# driver_board_v00.net
KiCad netlist of a schematic drawn in EAGLE
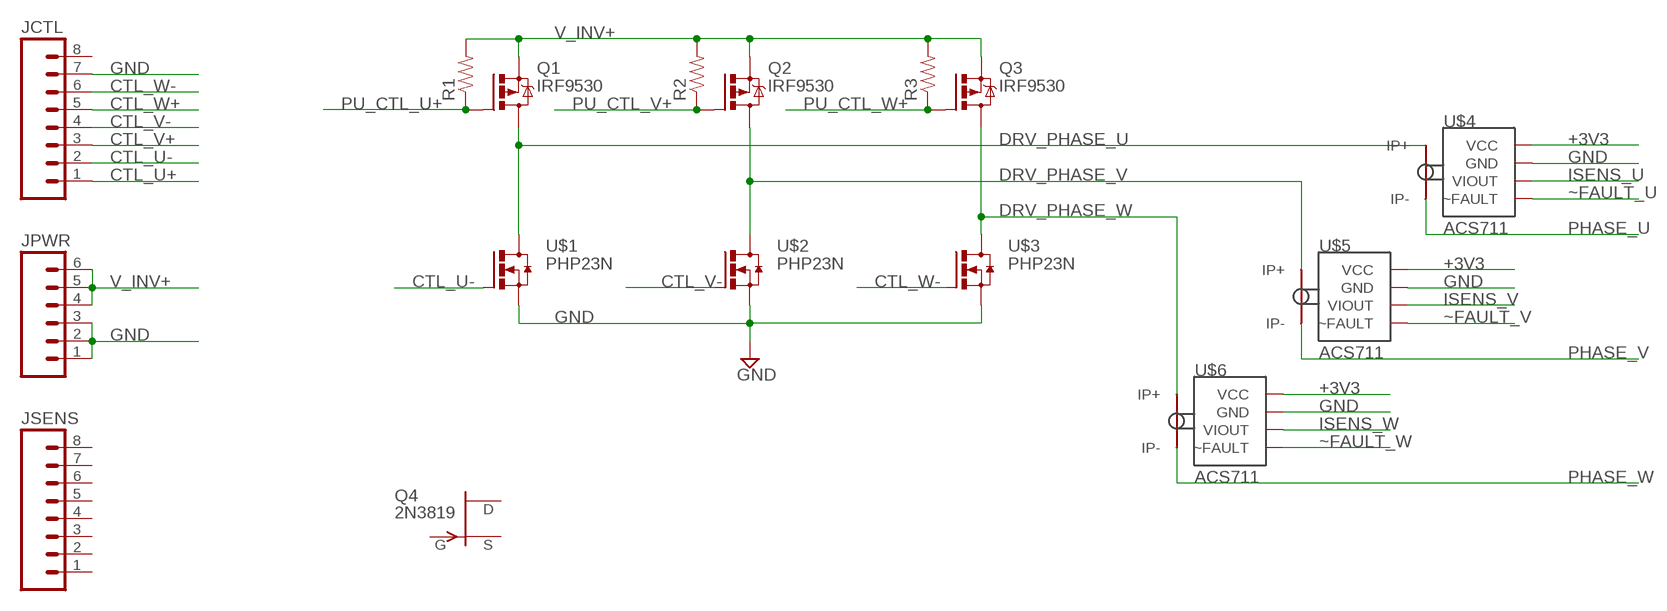
[diagram p0: schematic, sheet 1]

(export (version "E")
  (design (tool "Eeschema 10.0.6"))
  (components
    (comp (ref "JCTL")
      (value "M08LOCK")
      (footprint "eagle-import:1X08_LOCK")
      (libsource (lib "eagle-import") (part "M08LOCK"))
    )
    (comp (ref "JPWR")
      (value "M06LOCK")
      (footprint "eagle-import:1X06_LOCK")
      (libsource (lib "eagle-import") (part "M06LOCK"))
    )
    (comp (ref "JSENS")
      (value "M08LOCK")
      (footprint "eagle-import:1X08_LOCK")
      (libsource (lib "eagle-import") (part "M08LOCK"))
    )
    (comp (ref "Q1")
      (value "IRF9530")
      (footprint "eagle-import:TO220BV")
      (libsource (lib "eagle-import") (part "IRF9530"))
    )
    (comp (ref "Q2")
      (value "IRF9530")
      (footprint "eagle-import:TO220BV")
      (libsource (lib "eagle-import") (part "IRF9530"))
    )
    (comp (ref "Q3")
      (value "IRF9530")
      (footprint "eagle-import:TO220BV")
      (libsource (lib "eagle-import") (part "IRF9530"))
    )
    (comp (ref "Q4")
      (value "2N3819")
      (footprint "eagle-import:TO92")
      (libsource (lib "eagle-import") (part "2N3819"))
    )
    (comp (ref "R1")
      (value "RESISTOR0603")
      (footprint "eagle-import:0603-RES")
      (libsource (lib "eagle-import") (part "RESISTOR0603"))
    )
    (comp (ref "R2")
      (value "RESISTOR0603")
      (footprint "eagle-import:0603-RES")
      (libsource (lib "eagle-import") (part "RESISTOR0603"))
    )
    (comp (ref "R3")
      (value "RESISTOR0603")
      (footprint "eagle-import:0603-RES")
      (libsource (lib "eagle-import") (part "RESISTOR0603"))
    )
    (comp (ref "U$1")
      (value "PHP23N")
      (footprint "eagle-import:TO220BV")
      (libsource (lib "eagle-import") (part "PHP23N"))
    )
    (comp (ref "U$2")
      (value "PHP23N")
      (footprint "eagle-import:TO220BV")
      (libsource (lib "eagle-import") (part "PHP23N"))
    )
    (comp (ref "U$3")
      (value "PHP23N")
      (footprint "eagle-import:TO220BV")
      (libsource (lib "eagle-import") (part "PHP23N"))
    )
    (comp (ref "U$4")
      (value "ACS711")
      (footprint "eagle-import:12-WFQFN")
      (libsource (lib "eagle-import") (part "ACS711"))
    )
    (comp (ref "U$5")
      (value "ACS711")
      (footprint "eagle-import:12-WFQFN")
      (libsource (lib "eagle-import") (part "ACS711"))
    )
    (comp (ref "U$6")
      (value "ACS711")
      (footprint "eagle-import:12-WFQFN")
      (libsource (lib "eagle-import") (part "ACS711"))
    )
  )
  (nets
    (net (code "1") (name "/+3V3") (class "Default")
      (node (ref "U$4") (pin "P$12") (pinfunction "VCC_P$12") (pintype "bidirectional"))
      (node (ref "U$5") (pin "P$12") (pinfunction "VCC_P$12") (pintype "bidirectional"))
      (node (ref "U$6") (pin "P$12") (pinfunction "VCC_P$12") (pintype "bidirectional"))
    )
    (net (code "2") (name "/CTL_U+") (class "Default")
      (node (ref "JCTL") (pin "1") (pinfunction "1_1") (pintype "passive"))
    )
    (net (code "3") (name "/CTL_U-") (class "Default")
      (node (ref "JCTL") (pin "2") (pinfunction "2_2") (pintype "passive"))
      (node (ref "U$1") (pin "G") (pinfunction "G_G") (pintype "passive"))
    )
    (net (code "4") (name "/CTL_V+") (class "Default")
      (node (ref "JCTL") (pin "3") (pinfunction "3_3") (pintype "passive"))
    )
    (net (code "5") (name "/CTL_V-") (class "Default")
      (node (ref "JCTL") (pin "4") (pinfunction "4_4") (pintype "passive"))
      (node (ref "U$2") (pin "G") (pinfunction "G_G") (pintype "passive"))
    )
    (net (code "6") (name "/CTL_W+") (class "Default")
      (node (ref "JCTL") (pin "5") (pinfunction "5_5") (pintype "passive"))
    )
    (net (code "7") (name "/CTL_W-") (class "Default")
      (node (ref "JCTL") (pin "6") (pinfunction "6_6") (pintype "passive"))
      (node (ref "U$3") (pin "G") (pinfunction "G_G") (pintype "passive"))
    )
    (net (code "8") (name "/DRV_PHASE_U") (class "Default")
      (node (ref "Q1") (pin "D") (pinfunction "D_D") (pintype "passive"))
      (node (ref "U$1") (pin "D") (pinfunction "D_D") (pintype "passive"))
      (node (ref "U$4") (pin "P$1-2") (pinfunction "IP+_P$1-2") (pintype "bidirectional"))
    )
    (net (code "9") (name "/DRV_PHASE_V") (class "Default")
      (node (ref "Q2") (pin "D") (pinfunction "D_D") (pintype "passive"))
      (node (ref "U$2") (pin "D") (pinfunction "D_D") (pintype "passive"))
      (node (ref "U$5") (pin "P$1-2") (pinfunction "IP+_P$1-2") (pintype "bidirectional"))
    )
    (net (code "10") (name "/DRV_PHASE_W") (class "Default")
      (node (ref "Q3") (pin "D") (pinfunction "D_D") (pintype "passive"))
      (node (ref "U$3") (pin "D") (pinfunction "D_D") (pintype "passive"))
      (node (ref "U$6") (pin "P$1-2") (pinfunction "IP+_P$1-2") (pintype "bidirectional"))
    )
    (net (code "11") (name "/ISENS_U") (class "Default")
      (node (ref "U$4") (pin "P$11") (pinfunction "VIOUT_P$11") (pintype "bidirectional"))
    )
    (net (code "12") (name "/ISENS_V") (class "Default")
      (node (ref "U$5") (pin "P$11") (pinfunction "VIOUT_P$11") (pintype "bidirectional"))
    )
    (net (code "13") (name "/ISENS_W") (class "Default")
      (node (ref "U$6") (pin "P$11") (pinfunction "VIOUT_P$11") (pintype "bidirectional"))
    )
    (net (code "14") (name "/PHASE_U") (class "Default")
      (node (ref "U$4") (pin "P$3-4") (pinfunction "IP-_P$3-4") (pintype "output"))
    )
    (net (code "15") (name "/PHASE_V") (class "Default")
      (node (ref "U$5") (pin "P$3-4") (pinfunction "IP-_P$3-4") (pintype "output"))
    )
    (net (code "16") (name "/PHASE_W") (class "Default")
      (node (ref "U$6") (pin "P$3-4") (pinfunction "IP-_P$3-4") (pintype "output"))
    )
    (net (code "17") (name "/PU_CTL_U+") (class "Default")
      (node (ref "Q1") (pin "G") (pinfunction "G_G") (pintype "passive"))
      (node (ref "R1") (pin "1") (pinfunction "1_1") (pintype "passive"))
    )
    (net (code "18") (name "/PU_CTL_V+") (class "Default")
      (node (ref "Q2") (pin "G") (pinfunction "G_G") (pintype "passive"))
      (node (ref "R2") (pin "1") (pinfunction "1_1") (pintype "passive"))
    )
    (net (code "19") (name "/PU_CTL_W+") (class "Default")
      (node (ref "Q3") (pin "G") (pinfunction "G_G") (pintype "passive"))
      (node (ref "R3") (pin "1") (pinfunction "1_1") (pintype "passive"))
    )
    (net (code "20") (name "/V_INV+") (class "Default")
      (node (ref "JPWR") (pin "4") (pinfunction "4_4") (pintype "passive"))
      (node (ref "JPWR") (pin "5") (pinfunction "5_5") (pintype "passive"))
      (node (ref "JPWR") (pin "6") (pinfunction "6_6") (pintype "passive"))
      (node (ref "Q1") (pin "S") (pinfunction "S_S") (pintype "passive"))
      (node (ref "Q2") (pin "S") (pinfunction "S_S") (pintype "passive"))
      (node (ref "Q3") (pin "S") (pinfunction "S_S") (pintype "passive"))
      (node (ref "R1") (pin "2") (pinfunction "2_2") (pintype "passive"))
      (node (ref "R2") (pin "2") (pinfunction "2_2") (pintype "passive"))
      (node (ref "R3") (pin "2") (pinfunction "2_2") (pintype "passive"))
    )
    (net (code "21") (name "/~{FAULT_U}") (class "Default")
      (node (ref "U$4") (pin "P$6") (pinfunction "~{FAULT}_P$6") (pintype "bidirectional"))
    )
    (net (code "22") (name "/~{FAULT_V}") (class "Default")
      (node (ref "U$5") (pin "P$6") (pinfunction "~{FAULT}_P$6") (pintype "bidirectional"))
    )
    (net (code "23") (name "/~{FAULT_W}") (class "Default")
      (node (ref "U$6") (pin "P$6") (pinfunction "~{FAULT}_P$6") (pintype "bidirectional"))
    )
    (net (code "24") (name "GND") (class "Default")
      (node (ref "JCTL") (pin "7") (pinfunction "7_7") (pintype "passive"))
      (node (ref "JPWR") (pin "1") (pinfunction "1_1") (pintype "passive"))
      (node (ref "JPWR") (pin "2") (pinfunction "2_2") (pintype "passive"))
      (node (ref "JPWR") (pin "3") (pinfunction "3_3") (pintype "passive"))
      (node (ref "U$1") (pin "S") (pinfunction "S_S") (pintype "passive"))
      (node (ref "U$2") (pin "S") (pinfunction "S_S") (pintype "passive"))
      (node (ref "U$3") (pin "S") (pinfunction "S_S") (pintype "passive"))
      (node (ref "U$4") (pin "P$5") (pinfunction "GND_P$5") (pintype "bidirectional"))
      (node (ref "U$5") (pin "P$5") (pinfunction "GND_P$5") (pintype "bidirectional"))
      (node (ref "U$6") (pin "P$5") (pinfunction "GND_P$5") (pintype "bidirectional"))
    )
    (net (code "25") (name "unconnected-(JCTL-Pad8)") (class "Default")
      (node (ref "JCTL") (pin "8") (pinfunction "8_8") (pintype "passive"))
    )
    (net (code "26") (name "unconnected-(JSENS-Pad1)") (class "Default")
      (node (ref "JSENS") (pin "1") (pinfunction "1_1") (pintype "passive"))
    )
    (net (code "27") (name "unconnected-(JSENS-Pad2)") (class "Default")
      (node (ref "JSENS") (pin "2") (pinfunction "2_2") (pintype "passive"))
    )
    (net (code "28") (name "unconnected-(JSENS-Pad3)") (class "Default")
      (node (ref "JSENS") (pin "3") (pinfunction "3_3") (pintype "passive"))
    )
    (net (code "29") (name "unconnected-(JSENS-Pad4)") (class "Default")
      (node (ref "JSENS") (pin "4") (pinfunction "4_4") (pintype "passive"))
    )
    (net (code "30") (name "unconnected-(JSENS-Pad5)") (class "Default")
      (node (ref "JSENS") (pin "5") (pinfunction "5_5") (pintype "passive"))
    )
    (net (code "31") (name "unconnected-(JSENS-Pad6)") (class "Default")
      (node (ref "JSENS") (pin "6") (pinfunction "6_6") (pintype "passive"))
    )
    (net (code "32") (name "unconnected-(JSENS-Pad7)") (class "Default")
      (node (ref "JSENS") (pin "7") (pinfunction "7_7") (pintype "passive"))
    )
    (net (code "33") (name "unconnected-(JSENS-Pad8)") (class "Default")
      (node (ref "JSENS") (pin "8") (pinfunction "8_8") (pintype "passive"))
    )
    (net (code "34") (name "unconnected-(Q4-D-Pad1)") (class "Default")
      (node (ref "Q4") (pin "1") (pinfunction "D_1") (pintype "passive"))
    )
    (net (code "35") (name "unconnected-(Q4-G-Pad2)") (class "Default")
      (node (ref "Q4") (pin "2") (pinfunction "G_2") (pintype "passive"))
    )
    (net (code "36") (name "unconnected-(Q4-S-Pad3)") (class "Default")
      (node (ref "Q4") (pin "3") (pinfunction "S_3") (pintype "passive"))
    )
  )
)
